# MPU-6050_Main_SCH.net
KiCad netlist of a schematic drawn in Altium Designer
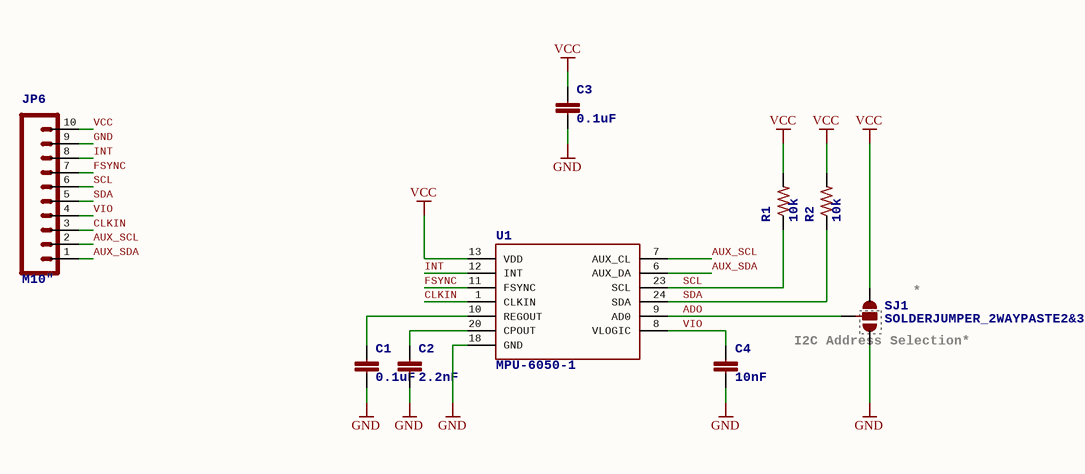
[diagram p0: MPU-6050_Main_SCH.SchDoc]

(export (version "E")
  (design (tool "Eeschema 10.0.6"))
  (components
    (comp (ref "C1")
      (value "0.1uF")
      (footprint "0603-CAP")
      (description "<b>Capacitor</b>\nStandard 0603 ceramic capacitor, and 0.1\" leaded capacitor.")
      (fields (field (name ">NAME") "C1") (field (name ">VALUE") "0.1uF"))
      (libsource (lib "SparkFun") (part "CAP0603-CAP"))
    )
    (comp (ref "C2")
      (value "2.2nF")
      (footprint "0603-CAP")
      (description "<b>Capacitor</b>\nStandard 0603 ceramic capacitor, and 0.1\" leaded capacitor.")
      (fields (field (name ">NAME") "C2") (field (name ">VALUE") "2.2nF"))
      (libsource (lib "SparkFun") (part "CAP0603-CAP"))
    )
    (comp (ref "C3")
      (value "0.1uF")
      (footprint "0603-CAP")
      (description "<b>Capacitor</b>\nStandard 0603 ceramic capacitor, and 0.1\" leaded capacitor.")
      (fields (field (name ">NAME") "C3") (field (name ">VALUE") "0.1uF"))
      (libsource (lib "SparkFun") (part "CAP0603-CAP"))
    )
    (comp (ref "C4")
      (value "10nF")
      (footprint "0603-CAP")
      (description "<b>Capacitor</b>\nStandard 0603 ceramic capacitor, and 0.1\" leaded capacitor.")
      (fields (field (name ">NAME") "C4") (field (name ">VALUE") "10nF"))
      (libsource (lib "SparkFun") (part "CAP0603-CAP"))
    )
    (comp (ref "JP6")
      (value "M10\"")
      (footprint "1X10")
      (fields (field (name ">VALUE") "M10\"") (field (name ">NAME") "JP6"))
      (libsource (lib "SparkFun") (part "M10{dblquote}"))
    )
    (comp (ref "R1")
      (value "10k")
      (footprint "0603-RES")
      (description "<b>Resistor</b>\nBasic schematic elements and footprints for 0603, 1206, and PTH resistors.")
      (fields (field (name ">NAME") "R1") (field (name ">VALUE") "10k"))
      (libsource (lib "SparkFun") (part "RESISTOR0603-RES"))
    )
    (comp (ref "R2")
      (value "10k")
      (footprint "0603-RES")
      (description "<b>Resistor</b>\nBasic schematic elements and footprints for 0603, 1206, and PTH resistors.")
      (fields (field (name ">NAME") "R2") (field (name ">VALUE") "10k"))
      (libsource (lib "SparkFun") (part "RESISTOR0603-RES"))
    )
    (comp (ref "SJ1")
      (value "SOLDERJUMPER_2WAYPASTE2&3")
      (footprint "SJ_3_PASTE2&3")
      (description "<b>Solder Jumper</b>\n2 way solder jumper")
      (fields (field (name ">NAME") "SJ1") (field (name ">VALUE") "SOLDERJUMPER_2WAYPASTE2&3"))
      (libsource (lib "SparkFun") (part "SOLDERJUMPER_2WAYPASTE2&3"))
    )
    (comp (ref "U1")
      (value "MPU-6050-1")
      (footprint "QFN-24-4MM2")
      (fields (field (name ">NAME") "U1") (field (name ">VALUE") "MPU-6050-1"))
      (libsource (lib "Testing") (part "MPU-6050-1"))
    )
  )
  (nets
    (net (code "1") (name "/ADO") (class "Default")
      (node (ref "SJ1") (pin "2") (pinfunction "2_2") (pintype "passive"))
      (node (ref "U1") (pin "9") (pinfunction "AD0_9") (pintype "passive"))
    )
    (net (code "2") (name "/AUX_SCL") (class "Default")
      (node (ref "JP6") (pin "2") (pinfunction "2_2") (pintype "passive"))
      (node (ref "U1") (pin "7") (pinfunction "AUX_CL_7") (pintype "passive"))
    )
    (net (code "3") (name "/AUX_SDA") (class "Default")
      (node (ref "JP6") (pin "1") (pinfunction "1_1") (pintype "passive"))
      (node (ref "U1") (pin "6") (pinfunction "AUX_DA_6") (pintype "passive"))
    )
    (net (code "4") (name "/CLKIN") (class "Default")
      (node (ref "JP6") (pin "3") (pinfunction "3_3") (pintype "passive"))
      (node (ref "U1") (pin "1") (pinfunction "CLKIN_1") (pintype "passive"))
    )
    (net (code "5") (name "/FSYNC") (class "Default")
      (node (ref "JP6") (pin "7") (pinfunction "7_7") (pintype "passive"))
      (node (ref "U1") (pin "11") (pinfunction "FSYNC_11") (pintype "passive"))
    )
    (net (code "6") (name "/INT") (class "Default")
      (node (ref "JP6") (pin "8") (pinfunction "8_8") (pintype "passive"))
      (node (ref "U1") (pin "12") (pinfunction "INT_12") (pintype "passive"))
    )
    (net (code "7") (name "/SCL") (class "Default")
      (node (ref "JP6") (pin "6") (pinfunction "6_6") (pintype "passive"))
      (node (ref "R1") (pin "1") (pinfunction "1_1") (pintype "passive"))
      (node (ref "U1") (pin "23") (pinfunction "SCL_23") (pintype "passive"))
    )
    (net (code "8") (name "/SDA") (class "Default")
      (node (ref "JP6") (pin "5") (pinfunction "5_5") (pintype "passive"))
      (node (ref "R2") (pin "1") (pinfunction "1_1") (pintype "passive"))
      (node (ref "U1") (pin "24") (pinfunction "SDA_24") (pintype "passive"))
    )
    (net (code "9") (name "/VIO") (class "Default")
      (node (ref "C4") (pin "1") (pinfunction "1_1") (pintype "passive"))
      (node (ref "JP6") (pin "4") (pinfunction "4_4") (pintype "passive"))
      (node (ref "U1") (pin "8") (pinfunction "VLOGIC_8") (pintype "passive"))
    )
    (net (code "10") (name "GND") (class "Default")
      (node (ref "C1") (pin "2") (pinfunction "2_2") (pintype "passive"))
      (node (ref "C2") (pin "2") (pinfunction "2_2") (pintype "passive"))
      (node (ref "C3") (pin "2") (pinfunction "2_2") (pintype "passive"))
      (node (ref "C4") (pin "2") (pinfunction "2_2") (pintype "passive"))
      (node (ref "JP6") (pin "9") (pinfunction "9_9") (pintype "passive"))
      (node (ref "SJ1") (pin "3") (pinfunction "3_3") (pintype "passive"))
      (node (ref "U1") (pin "18") (pinfunction "GND_18") (pintype "passive"))
    )
    (net (code "11") (name "Net-(U1-CPOUT)") (class "Default")
      (node (ref "C2") (pin "1") (pinfunction "1_1") (pintype "passive"))
      (node (ref "U1") (pin "20") (pinfunction "CPOUT_20") (pintype "passive"))
    )
    (net (code "12") (name "Net-(U1-REGOUT)") (class "Default")
      (node (ref "C1") (pin "1") (pinfunction "1_1") (pintype "passive"))
      (node (ref "U1") (pin "10") (pinfunction "REGOUT_10") (pintype "passive"))
    )
    (net (code "13") (name "VCC") (class "Default")
      (node (ref "C3") (pin "1") (pinfunction "1_1") (pintype "passive"))
      (node (ref "JP6") (pin "10") (pinfunction "10_10") (pintype "passive"))
      (node (ref "R1") (pin "2") (pinfunction "2_2") (pintype "passive"))
      (node (ref "R2") (pin "2") (pinfunction "2_2") (pintype "passive"))
      (node (ref "SJ1") (pin "1") (pinfunction "1_1") (pintype "passive"))
      (node (ref "U1") (pin "13") (pinfunction "VDD_13") (pintype "passive"))
    )
  )
)
